# 2_interface.net
KiCad netlist of a schematic drawn in Altium Designer
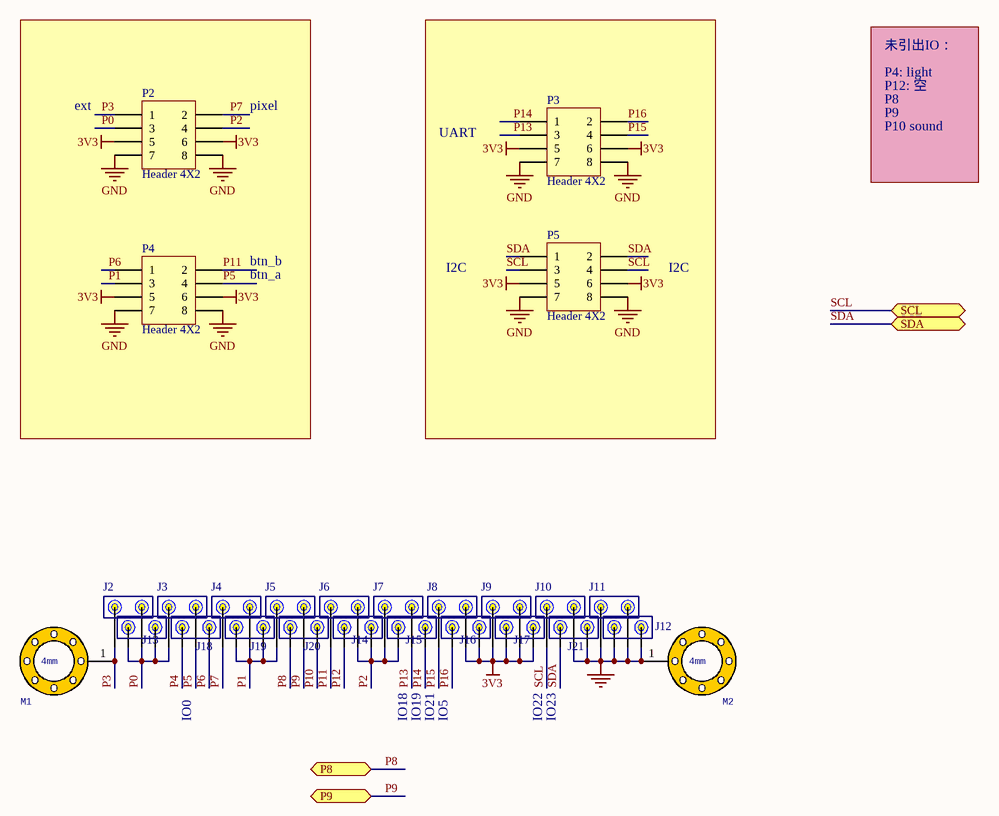
[diagram p0: 2.interface.SchDoc]

(export (version "E")
  (design (tool "Eeschema 10.0.6"))
  (components
    (comp (ref "J2") (value "~") (footprint "顶针座子（2.54MM）") (libsource (lib "Schlib1") (part "pogopin")))
    (comp (ref "J3") (value "~") (footprint "顶针座子（2.54MM）") (libsource (lib "Schlib1") (part "pogopin")))
    (comp (ref "J4") (value "~") (footprint "顶针座子（2.54MM）") (libsource (lib "Schlib1") (part "pogopin")))
    (comp (ref "J5") (value "~") (footprint "顶针座子（2.54MM）") (libsource (lib "Schlib1") (part "pogopin")))
    (comp (ref "J6") (value "~") (footprint "顶针座子（2.54MM）") (libsource (lib "Schlib1") (part "pogopin")))
    (comp (ref "J7") (value "~") (footprint "顶针座子（2.54MM）") (libsource (lib "Schlib1") (part "pogopin")))
    (comp (ref "J8") (value "~") (footprint "顶针座子（2.54MM）") (libsource (lib "Schlib1") (part "pogopin")))
    (comp (ref "J9") (value "~") (footprint "顶针座子（2.54MM）") (libsource (lib "Schlib1") (part "pogopin")))
    (comp (ref "J10") (value "~") (footprint "顶针座子（2.54MM）") (libsource (lib "Schlib1") (part "pogopin")))
    (comp (ref "J11") (value "~") (footprint "顶针座子（2.54MM）") (libsource (lib "Schlib1") (part "pogopin")))
    (comp (ref "J12") (value "~") (footprint "顶针座子（2.54MM）") (libsource (lib "Schlib1") (part "pogopin_32")))
    (comp (ref "J13") (value "~") (footprint "顶针座子（2.54MM）") (libsource (lib "Schlib1") (part "pogopin_32")))
    (comp (ref "J14") (value "~") (footprint "顶针座子（2.54MM）") (libsource (lib "Schlib1") (part "pogopin_32")))
    (comp (ref "J15") (value "~") (footprint "顶针座子（2.54MM）") (libsource (lib "Schlib1") (part "pogopin_32")))
    (comp (ref "J16") (value "~") (footprint "顶针座子（2.54MM）") (libsource (lib "Schlib1") (part "pogopin_32")))
    (comp (ref "J17") (value "~") (footprint "顶针座子（2.54MM）") (libsource (lib "Schlib1") (part "pogopin_32")))
    (comp (ref "J18") (value "~") (footprint "顶针座子（2.54MM）") (libsource (lib "Schlib1") (part "pogopin_32")))
    (comp (ref "J19") (value "~") (footprint "顶针座子（2.54MM）") (libsource (lib "Schlib1") (part "pogopin_32")))
    (comp (ref "J20") (value "~") (footprint "顶针座子（2.54MM）") (libsource (lib "Schlib1") (part "pogopin_32")))
    (comp (ref "J21") (value "~") (footprint "顶针座子（2.54MM）") (libsource (lib "Schlib1") (part "pogopin_32")))
    (comp (ref "M1") (value "4mm") (footprint "螺丝孔") (libsource (lib "labplus-connector") (part "screw")))
    (comp (ref "M2") (value "4mm") (footprint "螺丝孔") (libsource (lib "labplus-connector") (part "screw")))
    (comp (ref "P2")
      (value "Header 4X2")
      (footprint "HDR2X4")
      (description "Header, 4-Pin, Dual row")
      (fields (field (name "PUBLISHER") "Altium Limited"))
      (libsource (lib "Miscellaneous Connectors") (part "Header 4X2"))
    )
    (comp (ref "P3")
      (value "Header 4X2")
      (footprint "HDR2X4")
      (description "Header, 4-Pin, Dual row")
      (fields (field (name "PUBLISHER") "Altium Limited"))
      (libsource (lib "Miscellaneous Connectors") (part "Header 4X2"))
    )
    (comp (ref "P4")
      (value "Header 4X2")
      (footprint "HDR2X4")
      (description "Header, 4-Pin, Dual row")
      (fields (field (name "PUBLISHER") "Altium Limited"))
      (libsource (lib "Miscellaneous Connectors") (part "Header 4X2"))
    )
    (comp (ref "P5")
      (value "Header 4X2")
      (footprint "HDR2X4")
      (description "Header, 4-Pin, Dual row")
      (fields (field (name "PUBLISHER") "Altium Limited"))
      (libsource (lib "Miscellaneous Connectors") (part "Header 4X2"))
    )
  )
  (nets
    (net (code "1") (name "/P0") (class "Default")
      (node (ref "J13") (pin "1") (pinfunction "1_1") (pintype "passive"))
      (node (ref "J13") (pin "2") (pinfunction "2_2") (pintype "passive"))
      (node (ref "J2") (pin "2") (pinfunction "2_2") (pintype "passive"))
      (node (ref "J3") (pin "1") (pinfunction "1_1") (pintype "passive"))
      (node (ref "P2") (pin "3") (pinfunction "3_3") (pintype "passive"))
    )
    (net (code "2") (name "/P1") (class "Default")
      (node (ref "J19") (pin "1") (pinfunction "1_1") (pintype "passive"))
      (node (ref "J19") (pin "2") (pinfunction "2_2") (pintype "passive"))
      (node (ref "J4") (pin "2") (pinfunction "2_2") (pintype "passive"))
      (node (ref "J5") (pin "1") (pinfunction "1_1") (pintype "passive"))
      (node (ref "P4") (pin "3") (pinfunction "3_3") (pintype "passive"))
    )
    (net (code "3") (name "/P2") (class "Default")
      (node (ref "J14") (pin "2") (pinfunction "2_2") (pintype "passive"))
      (node (ref "J15") (pin "1") (pinfunction "1_1") (pintype "passive"))
      (node (ref "J6") (pin "2") (pinfunction "2_2") (pintype "passive"))
      (node (ref "J7") (pin "1") (pinfunction "1_1") (pintype "passive"))
      (node (ref "P2") (pin "4") (pinfunction "4_4") (pintype "passive"))
    )
    (net (code "4") (name "/P3") (class "Default")
      (node (ref "J2") (pin "1") (pinfunction "1_1") (pintype "passive"))
      (node (ref "M1") (pin "1") (pinfunction "1_1") (pintype "passive"))
      (node (ref "P2") (pin "1") (pinfunction "1_1") (pintype "passive"))
    )
    (net (code "5") (name "/P4") (class "Default")
      (node (ref "J18") (pin "1") (pinfunction "1_1") (pintype "passive"))
    )
    (net (code "6") (name "/P5") (class "Default")
      (node (ref "J3") (pin "2") (pinfunction "2_2") (pintype "passive"))
      (node (ref "P4") (pin "4") (pinfunction "4_4") (pintype "passive"))
    )
    (net (code "7") (name "/P6") (class "Default")
      (node (ref "J18") (pin "2") (pinfunction "2_2") (pintype "passive"))
      (node (ref "P4") (pin "1") (pinfunction "1_1") (pintype "passive"))
    )
    (net (code "8") (name "/P7") (class "Default")
      (node (ref "J4") (pin "1") (pinfunction "1_1") (pintype "passive"))
      (node (ref "P2") (pin "2") (pinfunction "2_2") (pintype "passive"))
    )
    (net (code "9") (name "/P8") (class "Default")
      (node (ref "J20") (pin "1") (pinfunction "1_1") (pintype "passive"))
    )
    (net (code "10") (name "/P9") (class "Default")
      (node (ref "J5") (pin "2") (pinfunction "2_2") (pintype "passive"))
    )
    (net (code "11") (name "/P10") (class "Default")
      (node (ref "J20") (pin "2") (pinfunction "2_2") (pintype "passive"))
    )
    (net (code "12") (name "/P11") (class "Default")
      (node (ref "J6") (pin "1") (pinfunction "1_1") (pintype "passive"))
      (node (ref "P4") (pin "2") (pinfunction "2_2") (pintype "passive"))
    )
    (net (code "13") (name "/P12") (class "Default")
      (node (ref "J14") (pin "1") (pinfunction "1_1") (pintype "passive"))
    )
    (net (code "14") (name "/P13") (class "Default")
      (node (ref "J7") (pin "2") (pinfunction "2_2") (pintype "passive"))
      (node (ref "P3") (pin "3") (pinfunction "3_3") (pintype "passive"))
    )
    (net (code "15") (name "/P14") (class "Default")
      (node (ref "J15") (pin "2") (pinfunction "2_2") (pintype "passive"))
      (node (ref "P3") (pin "1") (pinfunction "1_1") (pintype "passive"))
    )
    (net (code "16") (name "/P15") (class "Default")
      (node (ref "J8") (pin "1") (pinfunction "1_1") (pintype "passive"))
      (node (ref "P3") (pin "4") (pinfunction "4_4") (pintype "passive"))
    )
    (net (code "17") (name "/P16") (class "Default")
      (node (ref "J16") (pin "1") (pinfunction "1_1") (pintype "passive"))
      (node (ref "P3") (pin "2") (pinfunction "2_2") (pintype "passive"))
    )
    (net (code "18") (name "/SCL") (class "Default")
      (node (ref "J10") (pin "1") (pinfunction "1_1") (pintype "passive"))
      (node (ref "P5") (pin "3") (pinfunction "3_3") (pintype "passive"))
      (node (ref "P5") (pin "4") (pinfunction "4_4") (pintype "passive"))
    )
    (net (code "19") (name "/SDA") (class "Default")
      (node (ref "J21") (pin "1") (pinfunction "1_1") (pintype "passive"))
      (node (ref "P5") (pin "1") (pinfunction "1_1") (pintype "passive"))
      (node (ref "P5") (pin "2") (pinfunction "2_2") (pintype "passive"))
    )
    (net (code "20") (name "3V3") (class "Default")
      (node (ref "J16") (pin "2") (pinfunction "2_2") (pintype "passive"))
      (node (ref "J17") (pin "1") (pinfunction "1_1") (pintype "passive"))
      (node (ref "J17") (pin "2") (pinfunction "2_2") (pintype "passive"))
      (node (ref "J8") (pin "2") (pinfunction "2_2") (pintype "passive"))
      (node (ref "J9") (pin "1") (pinfunction "1_1") (pintype "passive"))
      (node (ref "J9") (pin "2") (pinfunction "2_2") (pintype "passive"))
      (node (ref "P2") (pin "5") (pinfunction "5_5") (pintype "passive"))
      (node (ref "P2") (pin "6") (pinfunction "6_6") (pintype "passive"))
      (node (ref "P3") (pin "5") (pinfunction "5_5") (pintype "passive"))
      (node (ref "P3") (pin "6") (pinfunction "6_6") (pintype "passive"))
      (node (ref "P4") (pin "5") (pinfunction "5_5") (pintype "passive"))
      (node (ref "P4") (pin "6") (pinfunction "6_6") (pintype "passive"))
      (node (ref "P5") (pin "5") (pinfunction "5_5") (pintype "passive"))
      (node (ref "P5") (pin "6") (pinfunction "6_6") (pintype "passive"))
    )
    (net (code "21") (name "GND") (class "Default")
      (node (ref "J10") (pin "2") (pinfunction "2_2") (pintype "passive"))
      (node (ref "J11") (pin "1") (pinfunction "1_1") (pintype "passive"))
      (node (ref "J11") (pin "2") (pinfunction "2_2") (pintype "passive"))
      (node (ref "J12") (pin "1") (pinfunction "1_1") (pintype "passive"))
      (node (ref "J12") (pin "2") (pinfunction "2_2") (pintype "passive"))
      (node (ref "J21") (pin "2") (pinfunction "2_2") (pintype "passive"))
      (node (ref "M2") (pin "1") (pinfunction "1_1") (pintype "passive"))
      (node (ref "P2") (pin "7") (pinfunction "7_7") (pintype "passive"))
      (node (ref "P2") (pin "8") (pinfunction "8_8") (pintype "passive"))
      (node (ref "P3") (pin "7") (pinfunction "7_7") (pintype "passive"))
      (node (ref "P3") (pin "8") (pinfunction "8_8") (pintype "passive"))
      (node (ref "P4") (pin "7") (pinfunction "7_7") (pintype "passive"))
      (node (ref "P4") (pin "8") (pinfunction "8_8") (pintype "passive"))
      (node (ref "P5") (pin "7") (pinfunction "7_7") (pintype "passive"))
      (node (ref "P5") (pin "8") (pinfunction "8_8") (pintype "passive"))
    )
  )
)
